# ao.net
KiCad netlist of a schematic drawn in Altium Designer
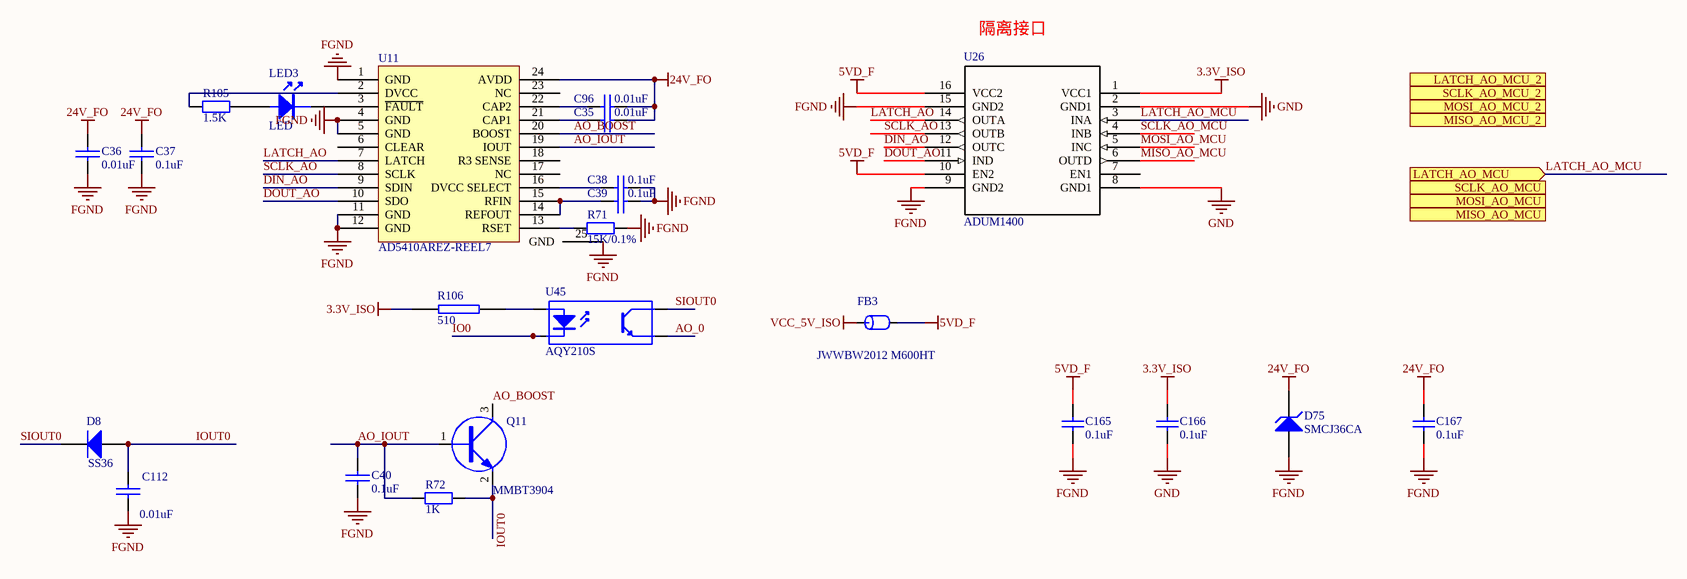
[diagram p0: ao.SchDoc]

(export (version "E")
  (design (tool "Eeschema 10.0.6"))
  (components
    (comp (ref "C35")
      (value "0.01uF")
      (footprint "0603C")
      (description "Capacitor")
      (libsource (lib "*") (part "CAP"))
    )
    (comp (ref "C36")
      (value "0.01uF")
      (footprint "0603C")
      (description "Capacitor")
      (libsource (lib "*") (part "CAP"))
    )
    (comp (ref "C37")
      (value "0.1uF")
      (footprint "0603C")
      (description "Capacitor")
      (libsource (lib "*") (part "CAP"))
    )
    (comp (ref "C38")
      (value "0.1uF")
      (footprint "0603C")
      (description "Capacitor")
      (libsource (lib "*") (part "CAP"))
    )
    (comp (ref "C39")
      (value "0.1uF")
      (footprint "0603C")
      (description "Capacitor")
      (libsource (lib "*") (part "CAP"))
    )
    (comp (ref "C40")
      (value "0.1uF")
      (footprint "0603C")
      (description "Capacitor")
      (libsource (lib "*") (part "CAP"))
    )
    (comp (ref "C96")
      (value "0.01uF")
      (footprint "0603C")
      (description "Capacitor")
      (libsource (lib "*") (part "CAP"))
    )
    (comp (ref "C112")
      (value "0.01uF")
      (footprint "0603C")
      (description "Capacitor")
      (libsource (lib "*") (part "CAP"))
    )
    (comp (ref "C165")
      (value "0.1uF")
      (footprint "0603C")
      (description "Capacitor")
      (fields (field (name "PUBLISHER") "Altium Limited"))
      (libsource (lib "Miscellaneous Devices") (part "Cap"))
    )
    (comp (ref "C166")
      (value "0.1uF")
      (footprint "0603C")
      (description "Capacitor")
      (fields (field (name "PUBLISHER") "Altium Limited"))
      (libsource (lib "Miscellaneous Devices") (part "Cap"))
    )
    (comp (ref "C167")
      (value "0.1uF")
      (footprint "0603C")
      (description "Capacitor")
      (fields (field (name "PUBLISHER") "Altium Limited"))
      (libsource (lib "Miscellaneous Devices") (part "Cap"))
    )
    (comp (ref "D8")
      (value "SS36")
      (footprint "sma")
      (description "1 Amp General Purpose Rectifier")
      (fields (field (name "PUBLISHER") "Altium Limited"))
      (libsource (lib "Miscellaneous Devices") (part "1N4001"))
    )
    (comp (ref "D75")
      (value "SMCJ36CA")
      (footprint "SMC")
      (description "SMBJ36CA")
      (fields (field (name "PUBLISHER") "Altium Limited"))
      (libsource (lib "Miscellaneous Devices") (part "D Zener"))
    )
    (comp (ref "FB3")
      (value "JWWBW2012 M600HT")
      (footprint "0805R")
      (libsource (lib "Schlib_20110825") (part "FB"))
    )
    (comp (ref "LED3") (value "LED") (footprint "0603LED") (libsource (lib "*") (part "LED")))
    (comp (ref "Q11")
      (value "MMBT3904")
      (footprint "SOT23-3")
      (libsource (lib "CenLib") (part "NPN_MMBT3904"))
    )
    (comp (ref "R71") (value "15K/0.1%") (footprint "0603R") (libsource (lib "MQlibrary") (part "Res0805M")))
    (comp (ref "R72") (value "1K") (footprint "0603R") (libsource (lib "MQlibrary") (part "Res0805M")))
    (comp (ref "R105") (value "1.5K") (footprint "0603R") (libsource (lib "MQlibrary") (part "Res0805M")))
    (comp (ref "R106") (value "510") (footprint "0603R") (libsource (lib "*") (part "RES2")))
    (comp (ref "U11")
      (value "AD5410AREZ-REEL7")
      (footprint "AD5410AREZ-REEL7")
      (libsource (lib "Schlib1") (part "AD5410AREZ-REEL7"))
    )
    (comp (ref "U26") (value "ADUM1400") (footprint "SOIC16") (libsource (lib "DI16") (part "ISO7241C")))
    (comp (ref "U45")
      (value "AQY210S")
      (footprint "sop4")
      (description "4-Pin Phototransistor Optocoupler")
      (fields (field (name "PUBLISHER") "Altium Limited"))
      (libsource (lib "Miscellaneous Devices") (part "Optoisolator1"))
    )
  )
  (nets
    (net (code "2") (name "/AO_0") (class "Default")
      (node (ref "U45") (pin "3") (pinfunction "E_3") (pintype "passive"))
    )
    (net (code "3") (name "/AO_BOOST") (class "Default")
      (node (ref "Q11") (pin "3") (pinfunction "C_3") (pintype "passive"))
      (node (ref "U11") (pin "20") (pinfunction "BOOST_20") (pintype "passive"))
    )
    (net (code "4") (name "/AO_IOUT") (class "Default")
      (node (ref "C40") (pin "2") (pinfunction "2_2") (pintype "passive"))
      (node (ref "Q11") (pin "1") (pinfunction "B_1") (pintype "passive"))
      (node (ref "R72") (pin "1") (pinfunction "1_1") (pintype "passive"))
      (node (ref "U11") (pin "19") (pinfunction "IOUT_19") (pintype "passive"))
    )
    (net (code "5") (name "/DIN_AO") (class "Default")
      (node (ref "U11") (pin "9") (pinfunction "SDIN_9") (pintype "passive"))
      (node (ref "U26") (pin "12") (pinfunction "OUTC_12") (pintype "output"))
    )
    (net (code "6") (name "/DOUT_AO") (class "Default")
      (node (ref "U11") (pin "10") (pinfunction "SDO_10") (pintype "passive"))
      (node (ref "U26") (pin "11") (pinfunction "IND_11") (pintype "input"))
    )
    (net (code "7") (name "/IO0") (class "Default")
      (node (ref "U45") (pin "2") (pinfunction "K_2") (pintype "passive"))
    )
    (net (code "8") (name "/IOUT0") (class "Default")
      (node (ref "C112") (pin "2") (pinfunction "2_2") (pintype "passive"))
      (node (ref "D8") (pin "1") (pinfunction "A_1") (pintype "passive"))
      (node (ref "Q11") (pin "2") (pinfunction "E_2") (pintype "passive"))
      (node (ref "R72") (pin "2") (pinfunction "2_2") (pintype "passive"))
    )
    (net (code "9") (name "/LATCH_AO") (class "Default")
      (node (ref "U11") (pin "7") (pinfunction "LATCH_7") (pintype "passive"))
      (node (ref "U26") (pin "14") (pinfunction "OUTA_14") (pintype "output"))
    )
    (net (code "10") (name "/LATCH_AO_MCU") (class "Default")
      (node (ref "U26") (pin "3") (pinfunction "INA_3") (pintype "input"))
    )
    (net (code "12") (name "/MISO_AO_MCU") (class "Default")
      (node (ref "U26") (pin "6") (pinfunction "OUTD_6") (pintype "output"))
    )
    (net (code "14") (name "/MOSI_AO_MCU") (class "Default")
      (node (ref "U26") (pin "5") (pinfunction "INC_5") (pintype "input"))
    )
    (net (code "16") (name "/SCLK_AO") (class "Default")
      (node (ref "U11") (pin "8") (pinfunction "SCLK_8") (pintype "passive"))
      (node (ref "U26") (pin "13") (pinfunction "OUTB_13") (pintype "output"))
    )
    (net (code "17") (name "/SCLK_AO_MCU") (class "Default")
      (node (ref "U26") (pin "4") (pinfunction "INB_4") (pintype "input"))
    )
    (net (code "19") (name "/SIOUT0") (class "Default")
      (node (ref "D8") (pin "2") (pinfunction "K_2") (pintype "passive"))
      (node (ref "U45") (pin "4") (pinfunction "C_4") (pintype "passive"))
    )
    (net (code "20") (name "3.3V_ISO") (class "Default")
      (node (ref "C166") (pin "2") (pinfunction "2_2") (pintype "passive"))
      (node (ref "R106") (pin "2") (pinfunction "2_2") (pintype "passive"))
      (node (ref "U26") (pin "1") (pinfunction "VCC1_1") (pintype "power_in"))
    )
    (net (code "21") (name "5VD_F") (class "Default")
      (node (ref "C165") (pin "2") (pinfunction "2_2") (pintype "passive"))
      (node (ref "FB3") (pin "2") (pintype "passive"))
      (node (ref "U26") (pin "10") (pinfunction "EN2_10") (pintype "passive"))
      (node (ref "U26") (pin "16") (pinfunction "VCC2_16") (pintype "power_in"))
    )
    (net (code "22") (name "24V_FO") (class "Default")
      (node (ref "C167") (pin "2") (pinfunction "2_2") (pintype "passive"))
      (node (ref "C35") (pin "2") (pinfunction "2_2") (pintype "passive"))
      (node (ref "C36") (pin "2") (pinfunction "2_2") (pintype "passive"))
      (node (ref "C37") (pin "2") (pinfunction "2_2") (pintype "passive"))
      (node (ref "C96") (pin "2") (pinfunction "2_2") (pintype "passive"))
      (node (ref "D75") (pin "2") (pinfunction "K_2") (pintype "passive"))
      (node (ref "U11") (pin "24") (pinfunction "AVDD_24") (pintype "passive"))
    )
    (net (code "23") (name "FGND") (class "Default")
      (node (ref "C112") (pin "1") (pinfunction "1_1") (pintype "passive"))
      (node (ref "C165") (pin "1") (pinfunction "1_1") (pintype "passive"))
      (node (ref "C167") (pin "1") (pinfunction "1_1") (pintype "passive"))
      (node (ref "C36") (pin "1") (pinfunction "1_1") (pintype "passive"))
      (node (ref "C37") (pin "1") (pinfunction "1_1") (pintype "passive"))
      (node (ref "C38") (pin "2") (pinfunction "2_2") (pintype "passive"))
      (node (ref "C39") (pin "2") (pinfunction "2_2") (pintype "passive"))
      (node (ref "C40") (pin "1") (pinfunction "1_1") (pintype "passive"))
      (node (ref "D75") (pin "1") (pinfunction "A_1") (pintype "passive"))
      (node (ref "R71") (pin "2") (pinfunction "2_2") (pintype "passive"))
      (node (ref "U11") (pin "1") (pinfunction "GND_1") (pintype "passive"))
      (node (ref "U11") (pin "11") (pinfunction "GND_11") (pintype "passive"))
      (node (ref "U11") (pin "12") (pinfunction "GND_12") (pintype "passive"))
      (node (ref "U11") (pin "25") (pinfunction "GND_25") (pintype "passive"))
      (node (ref "U11") (pin "4") (pinfunction "GND_4") (pintype "passive"))
      (node (ref "U11") (pin "5") (pinfunction "GND_5") (pintype "passive"))
      (node (ref "U26") (pin "15") (pinfunction "GND2_15") (pintype "power_in"))
      (node (ref "U26") (pin "9") (pinfunction "GND2_9") (pintype "power_in"))
    )
    (net (code "24") (name "GND") (class "Default")
      (node (ref "C166") (pin "1") (pinfunction "1_1") (pintype "passive"))
      (node (ref "U26") (pin "2") (pinfunction "GND1_2") (pintype "power_in"))
      (node (ref "U26") (pin "8") (pinfunction "GND1_8") (pintype "power_in"))
    )
    (net (code "25") (name "Net-(LED3-Pad1)") (class "Default")
      (node (ref "LED3") (pin "1") (pinfunction "1_1") (pintype "passive"))
      (node (ref "R105") (pin "2") (pinfunction "2_2") (pintype "passive"))
    )
    (net (code "26") (name "Net-(U11-CAP1)") (class "Default")
      (node (ref "C35") (pin "1") (pinfunction "1_1") (pintype "passive"))
      (node (ref "U11") (pin "21") (pinfunction "CAP1_21") (pintype "passive"))
    )
    (net (code "27") (name "Net-(U11-CAP2)") (class "Default")
      (node (ref "C96") (pin "1") (pinfunction "1_1") (pintype "passive"))
      (node (ref "U11") (pin "22") (pinfunction "CAP2_22") (pintype "passive"))
    )
    (net (code "28") (name "Net-(U11-DVCC)") (class "Default")
      (node (ref "R105") (pin "1") (pinfunction "1_1") (pintype "passive"))
      (node (ref "U11") (pin "2") (pinfunction "DVCC_2") (pintype "passive"))
    )
    (net (code "29") (name "Net-(U11-DVCC_SELECT)") (class "Default")
      (node (ref "C38") (pin "1") (pinfunction "1_1") (pintype "passive"))
      (node (ref "U11") (pin "16") (pinfunction "DVCC_SELECT_16") (pintype "passive"))
    )
    (net (code "30") (name "Net-(U11-REFOUT)") (class "Default")
      (node (ref "C39") (pin "1") (pinfunction "1_1") (pintype "passive"))
      (node (ref "U11") (pin "14") (pinfunction "REFOUT_14") (pintype "passive"))
      (node (ref "U11") (pin "15") (pinfunction "RFIN_15") (pintype "passive"))
    )
    (net (code "31") (name "Net-(U11-RSET)") (class "Default")
      (node (ref "R71") (pin "1") (pinfunction "1_1") (pintype "passive"))
      (node (ref "U11") (pin "13") (pinfunction "RSET_13") (pintype "passive"))
    )
    (net (code "32") (name "Net-(U11-~{FAULT})") (class "Default")
      (node (ref "LED3") (pin "2") (pinfunction "2_2") (pintype "passive"))
      (node (ref "U11") (pin "3") (pinfunction "~{FAULT}_3") (pintype "passive"))
    )
    (net (code "33") (name "Net-(U45-A)") (class "Default")
      (node (ref "R106") (pin "1") (pinfunction "1_1") (pintype "passive"))
      (node (ref "U45") (pin "1") (pinfunction "A_1") (pintype "passive"))
    )
    (net (code "34") (name "VCC_5V_ISO") (class "Default") (node (ref "FB3") (pin "1") (pintype "passive")))
    (net (code "35") (name "unconnected-(U11-CLEAR-Pad6)") (class "Default")
      (node (ref "U11") (pin "6") (pinfunction "CLEAR_6") (pintype "passive"))
    )
    (net (code "36") (name "unconnected-(U11-NC-Pad17)") (class "Default")
      (node (ref "U11") (pin "17") (pinfunction "NC_17") (pintype "passive"))
    )
    (net (code "37") (name "unconnected-(U11-NC-Pad23)") (class "Default")
      (node (ref "U11") (pin "23") (pinfunction "NC_23") (pintype "passive"))
    )
    (net (code "38") (name "unconnected-(U11-R3_SENSE-Pad18)") (class "Default")
      (node (ref "U11") (pin "18") (pinfunction "R3_SENSE_18") (pintype "passive"))
    )
    (net (code "39") (name "unconnected-(U26-EN1-Pad7)") (class "Default")
      (node (ref "U26") (pin "7") (pinfunction "EN1_7") (pintype "passive"))
    )
  )
)
